# untitled.net
KiCad netlist of a schematic drawn in EAGLE
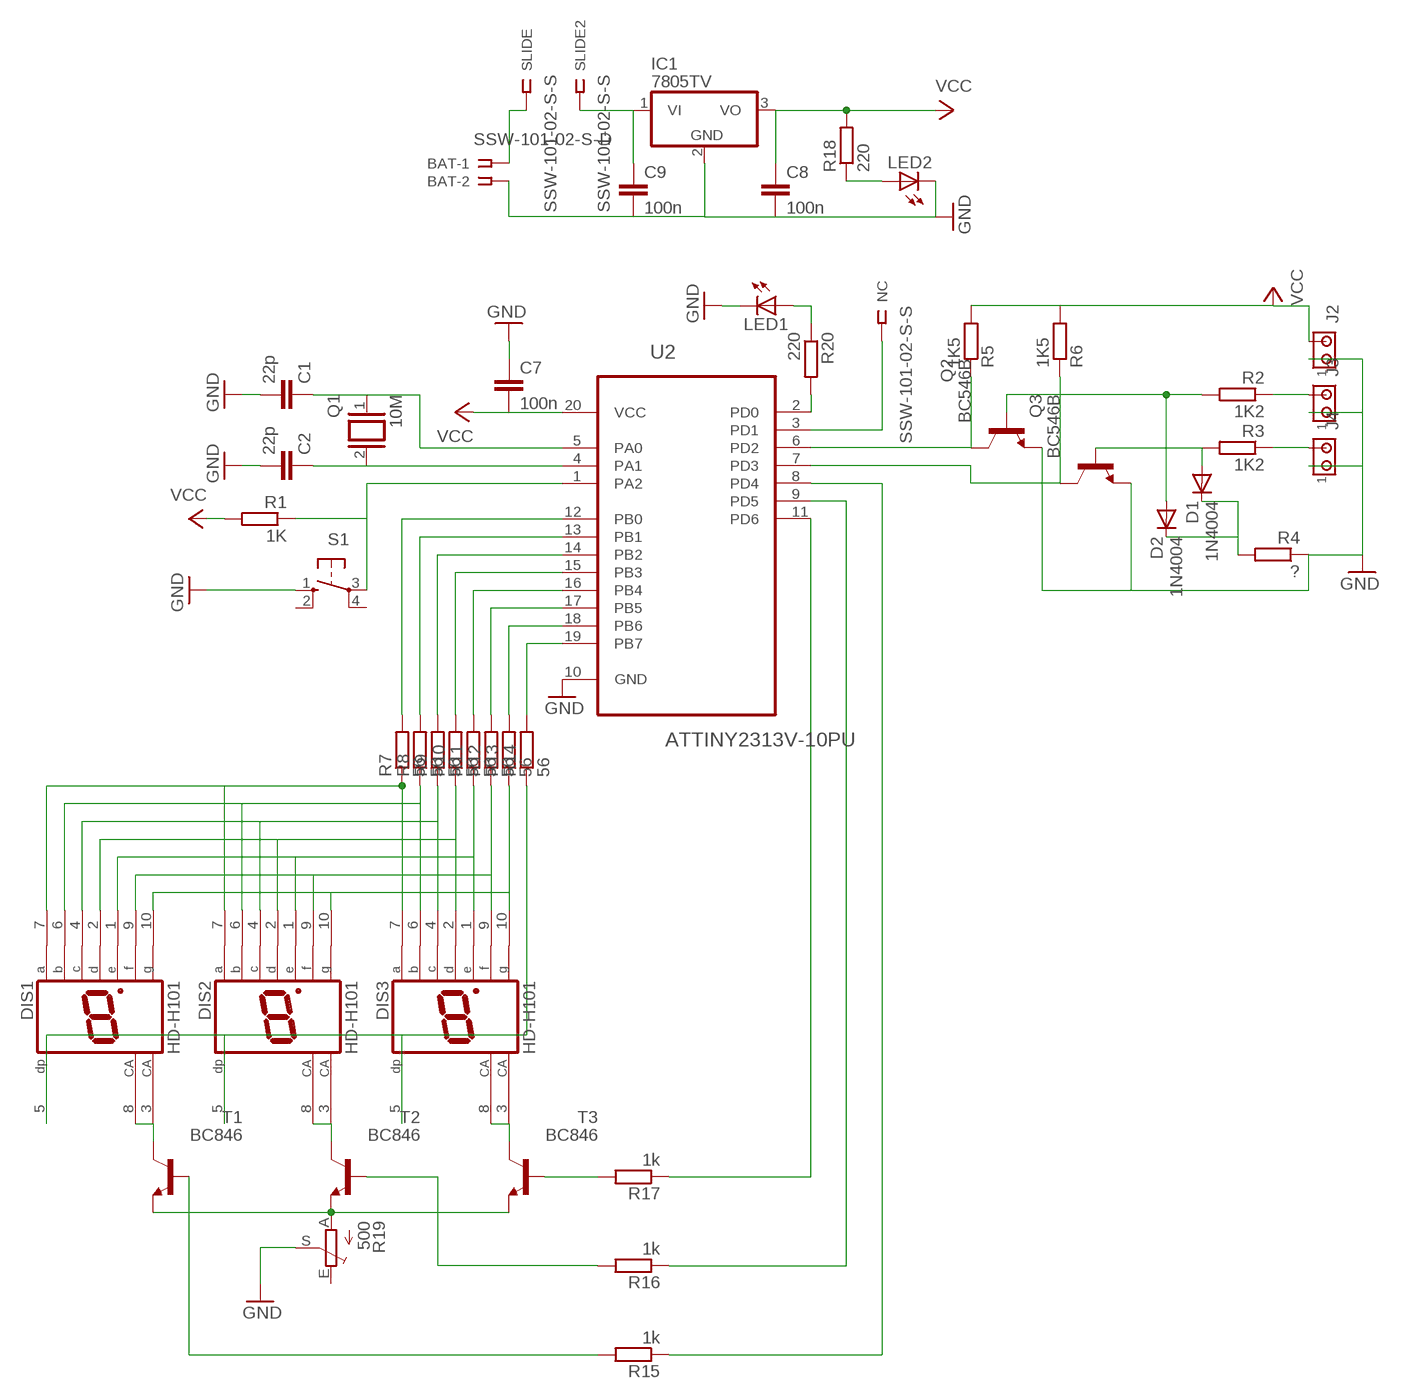
[diagram p0: schematic, sheet 1]

(export (version "E")
  (design (tool "Eeschema 10.0.6"))
  (components
    (comp (ref "BAT")
      (value "SSW-101-02-S-D")
      (footprint "eagle-import:SSW-101-02-S-D")
      (libsource (lib "eagle-import") (part "SSW-101-02-S-D"))
    )
    (comp (ref "C1")
      (value "22p")
      (footprint "eagle-import:C050-024X044")
      (libsource (lib "eagle-import") (part "C-EU050-024X044"))
    )
    (comp (ref "C2")
      (value "22p")
      (footprint "eagle-import:C050-024X044")
      (libsource (lib "eagle-import") (part "C-EU050-024X044"))
    )
    (comp (ref "C7")
      (value "100n")
      (footprint "eagle-import:C1206")
      (libsource (lib "eagle-import") (part "C-EUC1206"))
    )
    (comp (ref "C8")
      (value "100n")
      (footprint "eagle-import:C1206")
      (libsource (lib "eagle-import") (part "C-EUC1206"))
    )
    (comp (ref "C9")
      (value "100n")
      (footprint "eagle-import:C1206")
      (libsource (lib "eagle-import") (part "C-EUC1206"))
    )
    (comp (ref "D1")
      (value "1N4004")
      (footprint "eagle-import:DO41-10")
      (libsource (lib "eagle-import") (part "1N4004"))
    )
    (comp (ref "D2")
      (value "1N4004")
      (footprint "eagle-import:DO41-10")
      (libsource (lib "eagle-import") (part "1N4004"))
    )
    (comp (ref "DIS1")
      (value "HD-H101")
      (footprint "eagle-import:HDSP-M")
      (libsource (lib "eagle-import") (part "HD-H101"))
    )
    (comp (ref "DIS2")
      (value "HD-H101")
      (footprint "eagle-import:HDSP-M")
      (libsource (lib "eagle-import") (part "HD-H101"))
    )
    (comp (ref "DIS3")
      (value "HD-H101")
      (footprint "eagle-import:HDSP-M")
      (libsource (lib "eagle-import") (part "HD-H101"))
    )
    (comp (ref "IC1")
      (value "7805TV")
      (footprint "eagle-import:TO220V")
      (libsource (lib "eagle-import") (part "78TV05"))
    )
    (comp (ref "J2")
      (value "MTA02-100")
      (footprint "eagle-import:10X02MTA")
      (libsource (lib "eagle-import") (part "MTA02-100"))
    )
    (comp (ref "J3")
      (value "MTA02-100")
      (footprint "eagle-import:10X02MTA")
      (libsource (lib "eagle-import") (part "MTA02-100"))
    )
    (comp (ref "J4")
      (value "MTA02-100")
      (footprint "eagle-import:10X02MTA")
      (libsource (lib "eagle-import") (part "MTA02-100"))
    )
    (comp (ref "LED1")
      (value "LED3MM")
      (footprint "eagle-import:LED3MM")
      (libsource (lib "eagle-import") (part "LED3MM"))
    )
    (comp (ref "LED2")
      (value "LED3MM")
      (footprint "eagle-import:LED3MM")
      (libsource (lib "eagle-import") (part "LED3MM"))
    )
    (comp (ref "NC")
      (value "SSW-101-02-S-S")
      (footprint "eagle-import:SSW-101-02-S-S")
      (libsource (lib "eagle-import") (part "SSW-101-02-S-S"))
    )
    (comp (ref "Q1")
      (value "10M")
      (footprint "eagle-import:QS")
      (libsource (lib "eagle-import") (part "XTAL/S"))
    )
    (comp (ref "Q2")
      (value "BC546B")
      (footprint "eagle-import:TO92-EBC")
      (libsource (lib "eagle-import") (part "BC546B"))
    )
    (comp (ref "Q3")
      (value "BC546B")
      (footprint "eagle-import:TO92-EBC")
      (libsource (lib "eagle-import") (part "BC546B"))
    )
    (comp (ref "R1")
      (value "1K")
      (footprint "eagle-import:0204_7")
      (libsource (lib "eagle-import") (part "R-EU_0204/7"))
    )
    (comp (ref "R2")
      (value "1K2")
      (footprint "eagle-import:0204_7")
      (libsource (lib "eagle-import") (part "R-EU_0204/7"))
    )
    (comp (ref "R3")
      (value "1K2")
      (footprint "eagle-import:0204_7")
      (libsource (lib "eagle-import") (part "R-EU_0204/7"))
    )
    (comp (ref "R4")
      (value "?")
      (footprint "eagle-import:0204_7")
      (libsource (lib "eagle-import") (part "R-EU_0204/7"))
    )
    (comp (ref "R5")
      (value "1K5")
      (footprint "eagle-import:0204_7")
      (libsource (lib "eagle-import") (part "R-EU_0204/7"))
    )
    (comp (ref "R6")
      (value "1K5")
      (footprint "eagle-import:0204_7")
      (libsource (lib "eagle-import") (part "R-EU_0204/7"))
    )
    (comp (ref "R7")
      (value "56")
      (footprint "eagle-import:M1206")
      (libsource (lib "eagle-import") (part "R-EU_M1206"))
    )
    (comp (ref "R8")
      (value "56")
      (footprint "eagle-import:M1206")
      (libsource (lib "eagle-import") (part "R-EU_M1206"))
    )
    (comp (ref "R9")
      (value "56")
      (footprint "eagle-import:M1206")
      (libsource (lib "eagle-import") (part "R-EU_M1206"))
    )
    (comp (ref "R10")
      (value "56")
      (footprint "eagle-import:M1206")
      (libsource (lib "eagle-import") (part "R-EU_M1206"))
    )
    (comp (ref "R11")
      (value "56")
      (footprint "eagle-import:M1206")
      (libsource (lib "eagle-import") (part "R-EU_M1206"))
    )
    (comp (ref "R12")
      (value "56")
      (footprint "eagle-import:M1206")
      (libsource (lib "eagle-import") (part "R-EU_M1206"))
    )
    (comp (ref "R13")
      (value "56")
      (footprint "eagle-import:M1206")
      (libsource (lib "eagle-import") (part "R-EU_M1206"))
    )
    (comp (ref "R14")
      (value "56")
      (footprint "eagle-import:M1206")
      (libsource (lib "eagle-import") (part "R-EU_M1206"))
    )
    (comp (ref "R15")
      (value "1k")
      (footprint "eagle-import:M1206")
      (libsource (lib "eagle-import") (part "R-EU_M1206"))
    )
    (comp (ref "R16")
      (value "1k")
      (footprint "eagle-import:M1206")
      (libsource (lib "eagle-import") (part "R-EU_M1206"))
    )
    (comp (ref "R17")
      (value "1k")
      (footprint "eagle-import:M1206")
      (libsource (lib "eagle-import") (part "R-EU_M1206"))
    )
    (comp (ref "R18")
      (value "220")
      (footprint "eagle-import:M1206")
      (libsource (lib "eagle-import") (part "R-EU_M1206"))
    )
    (comp (ref "R19")
      (value "500")
      (footprint "eagle-import:CA6V")
      (libsource (lib "eagle-import") (part "TRIM_EU-CA6V"))
    )
    (comp (ref "R20")
      (value "220")
      (footprint "eagle-import:M1206")
      (libsource (lib "eagle-import") (part "R-EU_M1206"))
    )
    (comp (ref "S1")
      (value "10-XX")
      (footprint "eagle-import:B3F-10XX")
      (fields (field (name "MPN") "B3F-1000"))
      (libsource (lib "eagle-import") (part "10-XX"))
    )
    (comp (ref "SLIDE")
      (value "SSW-101-02-S-S")
      (footprint "eagle-import:SSW-101-02-S-S")
      (libsource (lib "eagle-import") (part "SSW-101-02-S-S"))
    )
    (comp (ref "SLIDE2")
      (value "SSW-101-02-S-S")
      (footprint "eagle-import:SSW-101-02-S-S")
      (libsource (lib "eagle-import") (part "SSW-101-02-S-S"))
    )
    (comp (ref "T1")
      (value "BC846")
      (footprint "eagle-import:SOT23")
      (libsource (lib "eagle-import") (part "BC846"))
    )
    (comp (ref "T2")
      (value "BC846")
      (footprint "eagle-import:SOT23")
      (libsource (lib "eagle-import") (part "BC846"))
    )
    (comp (ref "T3")
      (value "BC846")
      (footprint "eagle-import:SOT23")
      (libsource (lib "eagle-import") (part "BC846"))
    )
    (comp (ref "U2")
      (value "ATTINY2313V-10PU")
      (footprint "eagle-import:DIP254P762X533-20")
      (libsource (lib "eagle-import") (part "ATTINY2313V-10PU"))
    )
  )
  (nets
    (net (code "1") (name "GND") (class "Default")
      (node (ref "BAT") (pin "2") (pinfunction "1_2") (pintype "passive"))
      (node (ref "C1") (pin "2") (pinfunction "2_2") (pintype "passive"))
      (node (ref "C2") (pin "2") (pinfunction "2_2") (pintype "passive"))
      (node (ref "C7") (pin "1") (pinfunction "1_1") (pintype "passive"))
      (node (ref "C8") (pin "2") (pinfunction "2_2") (pintype "passive"))
      (node (ref "C9") (pin "2") (pinfunction "2_2") (pintype "passive"))
      (node (ref "IC1") (pin "2") (pinfunction "GND_2") (pintype "passive"))
      (node (ref "J2") (pin "1") (pinfunction "1_1") (pintype "passive"))
      (node (ref "J3") (pin "1") (pinfunction "1_1") (pintype "passive"))
      (node (ref "J4") (pin "1") (pinfunction "1_1") (pintype "passive"))
      (node (ref "LED1") (pin "K") (pinfunction "C_K") (pintype "passive"))
      (node (ref "LED2") (pin "K") (pinfunction "C_K") (pintype "passive"))
      (node (ref "Q2") (pin "E") (pinfunction "E_E") (pintype "passive"))
      (node (ref "Q3") (pin "E") (pinfunction "E_E") (pintype "passive"))
      (node (ref "R19") (pin "S") (pinfunction "S_S") (pintype "passive"))
      (node (ref "R4") (pin "1") (pinfunction "1_1") (pintype "passive"))
      (node (ref "S1") (pin "1") (pinfunction "S_1") (pintype "passive"))
      (node (ref "U2") (pin "10") (pinfunction "GND_10") (pintype "passive"))
    )
    (net (code "2") (name "Net-(BAT-Pad1)") (class "Default")
      (node (ref "BAT") (pin "1") (pinfunction "1_1") (pintype "passive"))
      (node (ref "SLIDE") (pin "1") (pinfunction "1_1") (pintype "passive"))
    )
    (net (code "3") (name "Net-(D1-PadA)") (class "Default")
      (node (ref "D1") (pin "A") (pinfunction "A_A") (pintype "passive"))
      (node (ref "Q3") (pin "B") (pinfunction "B_B") (pintype "passive"))
      (node (ref "R3") (pin "2") (pinfunction "2_2") (pintype "passive"))
    )
    (net (code "4") (name "Net-(D1-PadC)") (class "Default")
      (node (ref "D1") (pin "C") (pinfunction "C_C") (pintype "passive"))
      (node (ref "D2") (pin "C") (pinfunction "C_C") (pintype "passive"))
      (node (ref "R4") (pin "2") (pinfunction "2_2") (pintype "passive"))
    )
    (net (code "5") (name "Net-(D2-PadA)") (class "Default")
      (node (ref "D2") (pin "A") (pinfunction "A_A") (pintype "passive"))
      (node (ref "Q2") (pin "B") (pinfunction "B_B") (pintype "passive"))
      (node (ref "R2") (pin "2") (pinfunction "2_2") (pintype "passive"))
    )
    (net (code "6") (name "Net-(DIS1-A)") (class "Default")
      (node (ref "DIS1") (pin "7") (pinfunction "A_7") (pintype "passive"))
      (node (ref "DIS2") (pin "7") (pinfunction "A_7") (pintype "passive"))
      (node (ref "DIS3") (pin "7") (pinfunction "A_7") (pintype "passive"))
      (node (ref "R7") (pin "1") (pinfunction "1_1") (pintype "passive"))
    )
    (net (code "7") (name "Net-(DIS1-B)") (class "Default")
      (node (ref "DIS1") (pin "6") (pinfunction "B_6") (pintype "passive"))
      (node (ref "DIS2") (pin "6") (pinfunction "B_6") (pintype "passive"))
      (node (ref "DIS3") (pin "6") (pinfunction "B_6") (pintype "passive"))
      (node (ref "R8") (pin "1") (pinfunction "1_1") (pintype "passive"))
    )
    (net (code "8") (name "Net-(DIS1-C)") (class "Default")
      (node (ref "DIS1") (pin "4") (pinfunction "C_4") (pintype "passive"))
      (node (ref "DIS2") (pin "4") (pinfunction "C_4") (pintype "passive"))
      (node (ref "DIS3") (pin "4") (pinfunction "C_4") (pintype "passive"))
      (node (ref "R9") (pin "1") (pinfunction "1_1") (pintype "passive"))
    )
    (net (code "9") (name "Net-(DIS1-D)") (class "Default")
      (node (ref "DIS1") (pin "2") (pinfunction "D_2") (pintype "passive"))
      (node (ref "DIS2") (pin "2") (pinfunction "D_2") (pintype "passive"))
      (node (ref "DIS3") (pin "2") (pinfunction "D_2") (pintype "passive"))
      (node (ref "R10") (pin "1") (pinfunction "1_1") (pintype "passive"))
    )
    (net (code "10") (name "Net-(DIS1-DP)") (class "Default")
      (node (ref "DIS1") (pin "5") (pinfunction "DP_5") (pintype "passive"))
      (node (ref "DIS2") (pin "5") (pinfunction "DP_5") (pintype "passive"))
      (node (ref "DIS3") (pin "5") (pinfunction "DP_5") (pintype "passive"))
      (node (ref "R14") (pin "1") (pinfunction "1_1") (pintype "passive"))
    )
    (net (code "11") (name "Net-(DIS1-E)") (class "Default")
      (node (ref "DIS1") (pin "1") (pinfunction "E_1") (pintype "passive"))
      (node (ref "DIS2") (pin "1") (pinfunction "E_1") (pintype "passive"))
      (node (ref "DIS3") (pin "1") (pinfunction "E_1") (pintype "passive"))
      (node (ref "R11") (pin "1") (pinfunction "1_1") (pintype "passive"))
    )
    (net (code "12") (name "Net-(DIS1-F)") (class "Default")
      (node (ref "DIS1") (pin "9") (pinfunction "F_9") (pintype "passive"))
      (node (ref "DIS2") (pin "9") (pinfunction "F_9") (pintype "passive"))
      (node (ref "DIS3") (pin "9") (pinfunction "F_9") (pintype "passive"))
      (node (ref "R12") (pin "1") (pinfunction "1_1") (pintype "passive"))
    )
    (net (code "13") (name "Net-(DIS1-G)") (class "Default")
      (node (ref "DIS1") (pin "10") (pinfunction "G_10") (pintype "passive"))
      (node (ref "DIS2") (pin "10") (pinfunction "G_10") (pintype "passive"))
      (node (ref "DIS3") (pin "10") (pinfunction "G_10") (pintype "passive"))
      (node (ref "R13") (pin "1") (pinfunction "1_1") (pintype "passive"))
    )
    (net (code "14") (name "Net-(IC1-VI)") (class "Default")
      (node (ref "C9") (pin "1") (pinfunction "1_1") (pintype "passive"))
      (node (ref "IC1") (pin "1") (pinfunction "VI_1") (pintype "input"))
      (node (ref "SLIDE2") (pin "1") (pinfunction "1_1") (pintype "passive"))
    )
    (net (code "15") (name "Net-(J3-Pad2)") (class "Default")
      (node (ref "J3") (pin "2") (pinfunction "2_2") (pintype "passive"))
      (node (ref "R2") (pin "1") (pinfunction "1_1") (pintype "passive"))
    )
    (net (code "16") (name "Net-(J4-Pad2)") (class "Default")
      (node (ref "J4") (pin "2") (pinfunction "2_2") (pintype "passive"))
      (node (ref "R3") (pin "1") (pinfunction "1_1") (pintype "passive"))
    )
    (net (code "17") (name "Net-(LED1-PadA)") (class "Default")
      (node (ref "LED1") (pin "A") (pinfunction "A_A") (pintype "passive"))
      (node (ref "R20") (pin "1") (pinfunction "1_1") (pintype "passive"))
    )
    (net (code "18") (name "Net-(LED2-PadA)") (class "Default")
      (node (ref "LED2") (pin "A") (pinfunction "A_A") (pintype "passive"))
      (node (ref "R18") (pin "1") (pinfunction "1_1") (pintype "passive"))
    )
    (net (code "19") (name "Net-(S1-P)") (class "Default")
      (node (ref "R1") (pin "1") (pinfunction "1_1") (pintype "passive"))
      (node (ref "S1") (pin "3") (pinfunction "P_3") (pintype "passive"))
      (node (ref "U2") (pin "1") (pinfunction "PA2_1") (pintype "bidirectional"))
    )
    (net (code "20") (name "Net-(T1-B)") (class "Default")
      (node (ref "R15") (pin "2") (pinfunction "2_2") (pintype "passive"))
      (node (ref "T1") (pin "1") (pinfunction "B_1") (pintype "passive"))
    )
    (net (code "21") (name "Net-(T1-C)") (class "Default")
      (node (ref "DIS1") (pin "3") (pinfunction "CA_3") (pintype "passive"))
      (node (ref "DIS1") (pin "8") (pinfunction "CA_8") (pintype "passive"))
      (node (ref "T1") (pin "3") (pinfunction "C_3") (pintype "passive"))
    )
    (net (code "22") (name "Net-(T1-E)") (class "Default")
      (node (ref "R19") (pin "A") (pinfunction "A_A") (pintype "passive"))
      (node (ref "T1") (pin "2") (pinfunction "E_2") (pintype "passive"))
      (node (ref "T2") (pin "2") (pinfunction "E_2") (pintype "passive"))
      (node (ref "T3") (pin "2") (pinfunction "E_2") (pintype "passive"))
    )
    (net (code "23") (name "Net-(T2-B)") (class "Default")
      (node (ref "R16") (pin "2") (pinfunction "2_2") (pintype "passive"))
      (node (ref "T2") (pin "1") (pinfunction "B_1") (pintype "passive"))
    )
    (net (code "24") (name "Net-(T2-C)") (class "Default")
      (node (ref "DIS2") (pin "3") (pinfunction "CA_3") (pintype "passive"))
      (node (ref "DIS2") (pin "8") (pinfunction "CA_8") (pintype "passive"))
      (node (ref "T2") (pin "3") (pinfunction "C_3") (pintype "passive"))
    )
    (net (code "25") (name "Net-(T3-B)") (class "Default")
      (node (ref "R17") (pin "2") (pinfunction "2_2") (pintype "passive"))
      (node (ref "T3") (pin "1") (pinfunction "B_1") (pintype "passive"))
    )
    (net (code "26") (name "Net-(T3-C)") (class "Default")
      (node (ref "DIS3") (pin "3") (pinfunction "CA_3") (pintype "passive"))
      (node (ref "DIS3") (pin "8") (pinfunction "CA_8") (pintype "passive"))
      (node (ref "T3") (pin "3") (pinfunction "C_3") (pintype "passive"))
    )
    (net (code "27") (name "Net-(U2-PA0)") (class "Default")
      (node (ref "C1") (pin "1") (pinfunction "1_1") (pintype "passive"))
      (node (ref "Q1") (pin "1") (pinfunction "1_1") (pintype "passive"))
      (node (ref "U2") (pin "5") (pinfunction "PA0_5") (pintype "bidirectional"))
    )
    (net (code "28") (name "Net-(U2-PA1)") (class "Default")
      (node (ref "C2") (pin "1") (pinfunction "1_1") (pintype "passive"))
      (node (ref "Q1") (pin "2") (pinfunction "2_2") (pintype "passive"))
      (node (ref "U2") (pin "4") (pinfunction "PA1_4") (pintype "bidirectional"))
    )
    (net (code "29") (name "Net-(U2-PB0)") (class "Default")
      (node (ref "R7") (pin "2") (pinfunction "2_2") (pintype "passive"))
      (node (ref "U2") (pin "12") (pinfunction "PB0_12") (pintype "bidirectional"))
    )
    (net (code "30") (name "Net-(U2-PB1)") (class "Default")
      (node (ref "R8") (pin "2") (pinfunction "2_2") (pintype "passive"))
      (node (ref "U2") (pin "13") (pinfunction "PB1_13") (pintype "bidirectional"))
    )
    (net (code "31") (name "Net-(U2-PB2)") (class "Default")
      (node (ref "R9") (pin "2") (pinfunction "2_2") (pintype "passive"))
      (node (ref "U2") (pin "14") (pinfunction "PB2_14") (pintype "bidirectional"))
    )
    (net (code "32") (name "Net-(U2-PB3)") (class "Default")
      (node (ref "R10") (pin "2") (pinfunction "2_2") (pintype "passive"))
      (node (ref "U2") (pin "15") (pinfunction "PB3_15") (pintype "bidirectional"))
    )
    (net (code "33") (name "Net-(U2-PB4)") (class "Default")
      (node (ref "R11") (pin "2") (pinfunction "2_2") (pintype "passive"))
      (node (ref "U2") (pin "16") (pinfunction "PB4_16") (pintype "bidirectional"))
    )
    (net (code "34") (name "Net-(U2-PB5)") (class "Default")
      (node (ref "R12") (pin "2") (pinfunction "2_2") (pintype "passive"))
      (node (ref "U2") (pin "17") (pinfunction "PB5_17") (pintype "bidirectional"))
    )
    (net (code "35") (name "Net-(U2-PB6)") (class "Default")
      (node (ref "R13") (pin "2") (pinfunction "2_2") (pintype "passive"))
      (node (ref "U2") (pin "18") (pinfunction "PB6_18") (pintype "bidirectional"))
    )
    (net (code "36") (name "Net-(U2-PB7)") (class "Default")
      (node (ref "R14") (pin "2") (pinfunction "2_2") (pintype "passive"))
      (node (ref "U2") (pin "19") (pinfunction "PB7_19") (pintype "bidirectional"))
    )
    (net (code "37") (name "Net-(U2-PD0)") (class "Default")
      (node (ref "R20") (pin "2") (pinfunction "2_2") (pintype "passive"))
      (node (ref "U2") (pin "2") (pinfunction "PD0_2") (pintype "bidirectional"))
    )
    (net (code "38") (name "Net-(U2-PD1)") (class "Default")
      (node (ref "NC") (pin "1") (pinfunction "1_1") (pintype "passive"))
      (node (ref "U2") (pin "3") (pinfunction "PD1_3") (pintype "bidirectional"))
    )
    (net (code "39") (name "Net-(U2-PD2)") (class "Default")
      (node (ref "Q2") (pin "C") (pinfunction "C_C") (pintype "passive"))
      (node (ref "R5") (pin "1") (pinfunction "1_1") (pintype "passive"))
      (node (ref "U2") (pin "6") (pinfunction "PD2_6") (pintype "bidirectional"))
    )
    (net (code "40") (name "Net-(U2-PD3)") (class "Default")
      (node (ref "Q3") (pin "C") (pinfunction "C_C") (pintype "passive"))
      (node (ref "R6") (pin "1") (pinfunction "1_1") (pintype "passive"))
      (node (ref "U2") (pin "7") (pinfunction "PD3_7") (pintype "bidirectional"))
    )
    (net (code "41") (name "Net-(U2-PD4)") (class "Default")
      (node (ref "R15") (pin "1") (pinfunction "1_1") (pintype "passive"))
      (node (ref "U2") (pin "8") (pinfunction "PD4_8") (pintype "bidirectional"))
    )
    (net (code "42") (name "Net-(U2-PD5)") (class "Default")
      (node (ref "R16") (pin "1") (pinfunction "1_1") (pintype "passive"))
      (node (ref "U2") (pin "9") (pinfunction "PD5_9") (pintype "bidirectional"))
    )
    (net (code "43") (name "Net-(U2-PD6)") (class "Default")
      (node (ref "R17") (pin "1") (pinfunction "1_1") (pintype "passive"))
      (node (ref "U2") (pin "11") (pinfunction "PD6_11") (pintype "bidirectional"))
    )
    (net (code "44") (name "VCC") (class "Default")
      (node (ref "C7") (pin "2") (pinfunction "2_2") (pintype "passive"))
      (node (ref "C8") (pin "1") (pinfunction "1_1") (pintype "passive"))
      (node (ref "IC1") (pin "3") (pinfunction "VO_3") (pintype "passive"))
      (node (ref "J2") (pin "2") (pinfunction "2_2") (pintype "passive"))
      (node (ref "R1") (pin "2") (pinfunction "2_2") (pintype "passive"))
      (node (ref "R18") (pin "2") (pinfunction "2_2") (pintype "passive"))
      (node (ref "R5") (pin "2") (pinfunction "2_2") (pintype "passive"))
      (node (ref "R6") (pin "2") (pinfunction "2_2") (pintype "passive"))
      (node (ref "U2") (pin "20") (pinfunction "VCC_20") (pintype "power_in"))
    )
    (net (code "45") (name "unconnected-(R19-PadE)") (class "Default")
      (node (ref "R19") (pin "E") (pinfunction "E_E") (pintype "passive"))
    )
    (net (code "46") (name "unconnected-(S1-P1-Pad4)") (class "Default")
      (node (ref "S1") (pin "4") (pinfunction "P1_4") (pintype "passive"))
    )
    (net (code "47") (name "unconnected-(S1-S1-Pad2)") (class "Default")
      (node (ref "S1") (pin "2") (pinfunction "S1_2") (pintype "passive"))
    )
  )
)
